# lv_io_pressure.net
KiCad netlist of a schematic drawn in Altium Designer
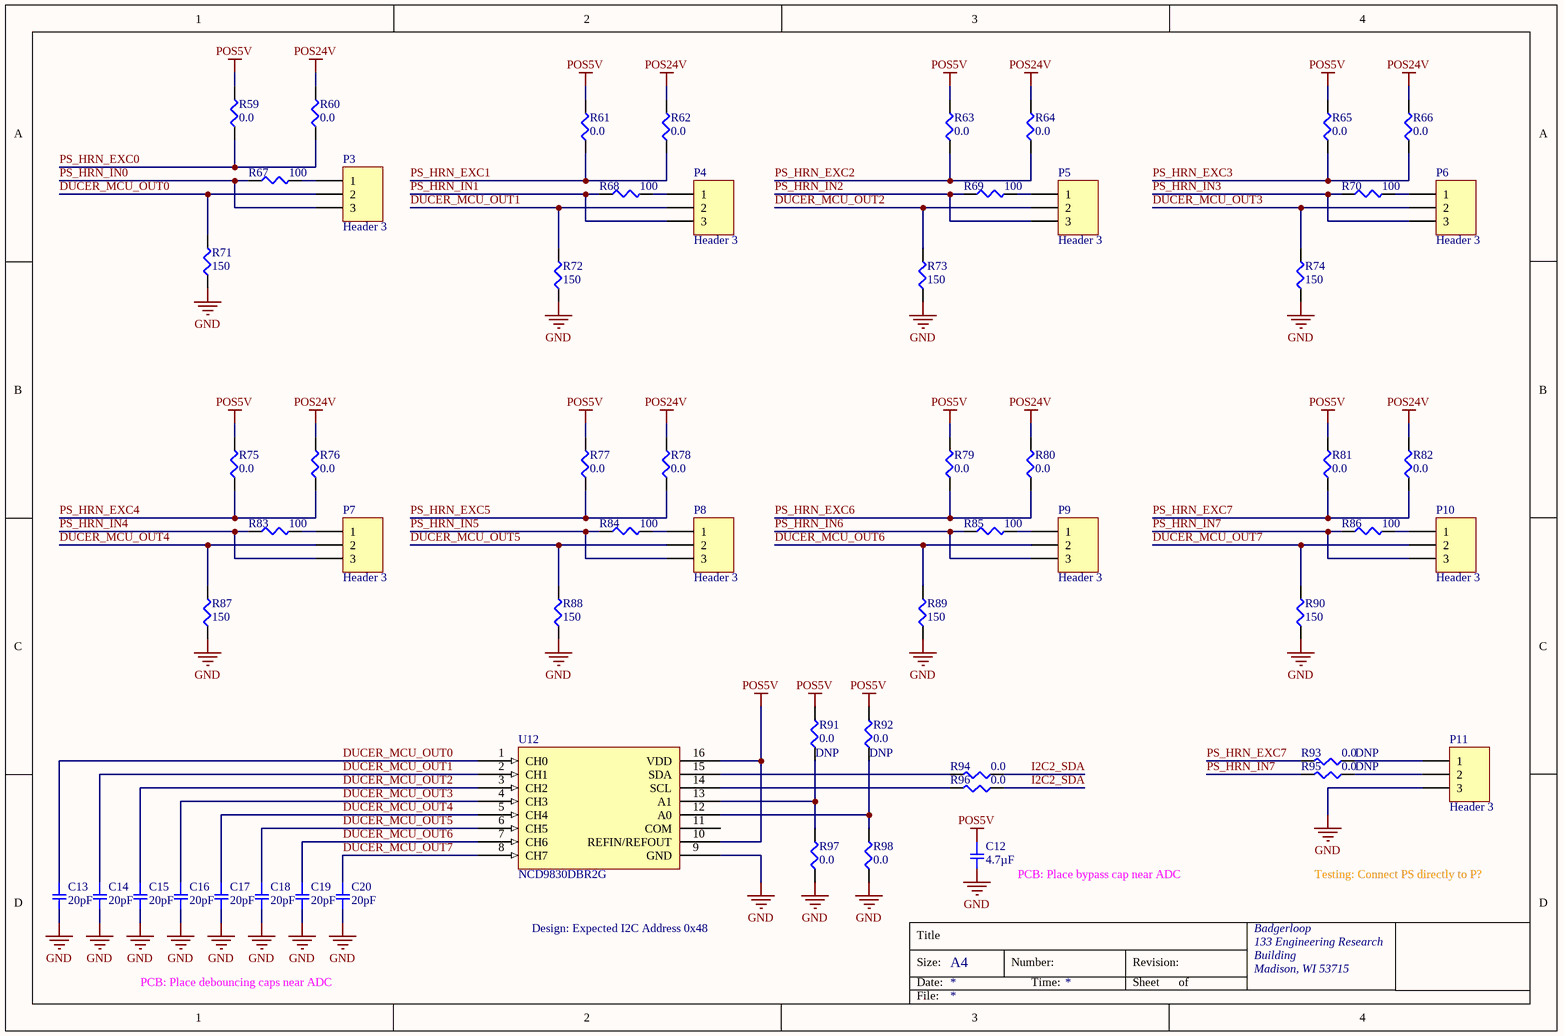
[diagram p0: lv_io_pressure.SchDoc]

(export (version "E")
  (design (tool "Eeschema 10.0.6"))
  (components
    (comp (ref "C12")
      (value "4.7µF")
      (footprint "SMD-0805C")
      (description "CAP CER 4.7UF 6.3V X5R 0805")
      (fields
        (field (name "DIGI-KEY PART NUMBER") "490-9749-1-ND")
        (field (name "PART NUMBER") "GRM21BR60J475KA11L")
      )
      (libsource (lib "capacitor") (part "GRM21BR60J475KA11L"))
    )
    (comp (ref "C13")
      (value "20pF")
      (footprint "SMD-0402C")
      (description "CAP CER 20PF 50V NP0 0402")
      (fields
        (field (name "DIGI-KEY PART NUMBER") "490-3120-1-ND")
        (field (name "PART NUMBER") "GJM1555C1H200JB01D")
      )
      (libsource (lib "capacitor") (part "GJM1555C1H200JB01D"))
    )
    (comp (ref "C14")
      (value "20pF")
      (footprint "SMD-0402C")
      (description "CAP CER 20PF 50V NP0 0402")
      (fields
        (field (name "DIGI-KEY PART NUMBER") "490-3120-1-ND")
        (field (name "PART NUMBER") "GJM1555C1H200JB01D")
      )
      (libsource (lib "capacitor") (part "GJM1555C1H200JB01D"))
    )
    (comp (ref "C15")
      (value "20pF")
      (footprint "SMD-0402C")
      (description "CAP CER 20PF 50V NP0 0402")
      (fields
        (field (name "DIGI-KEY PART NUMBER") "490-3120-1-ND")
        (field (name "PART NUMBER") "GJM1555C1H200JB01D")
      )
      (libsource (lib "capacitor") (part "GJM1555C1H200JB01D"))
    )
    (comp (ref "C16")
      (value "20pF")
      (footprint "SMD-0402C")
      (description "CAP CER 20PF 50V NP0 0402")
      (fields
        (field (name "DIGI-KEY PART NUMBER") "490-3120-1-ND")
        (field (name "PART NUMBER") "GJM1555C1H200JB01D")
      )
      (libsource (lib "capacitor") (part "GJM1555C1H200JB01D"))
    )
    (comp (ref "C17")
      (value "20pF")
      (footprint "SMD-0402C")
      (description "CAP CER 20PF 50V NP0 0402")
      (fields
        (field (name "DIGI-KEY PART NUMBER") "490-3120-1-ND")
        (field (name "PART NUMBER") "GJM1555C1H200JB01D")
      )
      (libsource (lib "capacitor") (part "GJM1555C1H200JB01D"))
    )
    (comp (ref "C18")
      (value "20pF")
      (footprint "SMD-0402C")
      (description "CAP CER 20PF 50V NP0 0402")
      (fields
        (field (name "DIGI-KEY PART NUMBER") "490-3120-1-ND")
        (field (name "PART NUMBER") "GJM1555C1H200JB01D")
      )
      (libsource (lib "capacitor") (part "GJM1555C1H200JB01D"))
    )
    (comp (ref "C19")
      (value "20pF")
      (footprint "SMD-0402C")
      (description "CAP CER 20PF 50V NP0 0402")
      (fields
        (field (name "DIGI-KEY PART NUMBER") "490-3120-1-ND")
        (field (name "PART NUMBER") "GJM1555C1H200JB01D")
      )
      (libsource (lib "capacitor") (part "GJM1555C1H200JB01D"))
    )
    (comp (ref "C20")
      (value "20pF")
      (footprint "SMD-0402C")
      (description "CAP CER 20PF 50V NP0 0402")
      (fields
        (field (name "DIGI-KEY PART NUMBER") "490-3120-1-ND")
        (field (name "PART NUMBER") "GJM1555C1H200JB01D")
      )
      (libsource (lib "capacitor") (part "GJM1555C1H200JB01D"))
    )
    (comp (ref "P3")
      (value "Header 3")
      (footprint "Pin Header 1x3 TH Pitch 2.54mm")
      (description "Header, 3-Pin")
      (fields (field (name "PUBLISHER") "Altium Limited"))
      (libsource (lib "connector") (part "Header 3"))
    )
    (comp (ref "P4")
      (value "Header 3")
      (footprint "Pin Header 1x3 TH Pitch 2.54mm")
      (description "Header, 3-Pin")
      (fields (field (name "PUBLISHER") "Altium Limited"))
      (libsource (lib "connector") (part "Header 3"))
    )
    (comp (ref "P5")
      (value "Header 3")
      (footprint "Pin Header 1x3 TH Pitch 2.54mm")
      (description "Header, 3-Pin")
      (fields (field (name "PUBLISHER") "Altium Limited"))
      (libsource (lib "connector") (part "Header 3"))
    )
    (comp (ref "P6")
      (value "Header 3")
      (footprint "Pin Header 1x3 TH Pitch 2.54mm")
      (description "Header, 3-Pin")
      (fields (field (name "PUBLISHER") "Altium Limited"))
      (libsource (lib "connector") (part "Header 3"))
    )
    (comp (ref "P7")
      (value "Header 3")
      (footprint "Pin Header 1x3 TH Pitch 2.54mm")
      (description "Header, 3-Pin")
      (fields (field (name "PUBLISHER") "Altium Limited"))
      (libsource (lib "connector") (part "Header 3"))
    )
    (comp (ref "P8")
      (value "Header 3")
      (footprint "Pin Header 1x3 TH Pitch 2.54mm")
      (description "Header, 3-Pin")
      (fields (field (name "PUBLISHER") "Altium Limited"))
      (libsource (lib "connector") (part "Header 3"))
    )
    (comp (ref "P9")
      (value "Header 3")
      (footprint "Pin Header 1x3 TH Pitch 2.54mm")
      (description "Header, 3-Pin")
      (fields (field (name "PUBLISHER") "Altium Limited"))
      (libsource (lib "connector") (part "Header 3"))
    )
    (comp (ref "P10")
      (value "Header 3")
      (footprint "Pin Header 1x3 TH Pitch 2.54mm")
      (description "Header, 3-Pin")
      (fields (field (name "PUBLISHER") "Altium Limited"))
      (libsource (lib "connector") (part "Header 3"))
    )
    (comp (ref "P11")
      (value "Header 3")
      (footprint "Pin Header 1x3 TH Pitch 2.54mm")
      (description "Header, 3-Pin")
      (fields (field (name "PUBLISHER") "Altium Limited"))
      (libsource (lib "connector") (part "Header 3"))
    )
    (comp (ref "R59")
      (value "0.0")
      (footprint "SMD-0402-RES")
      (description "RES SMD 0.0OHM JUMPER 1/10W 0402")
      (fields (field (name "PART NUMBER") "ERJ-2GE0R00X") (field (name "DIGI-KEY PART NUMBER") "P0.0JCT-ND"))
      (libsource (lib "resistor") (part "ERJ-2GE0R00X"))
    )
    (comp (ref "R60")
      (value "0.0")
      (footprint "SMD-0402-RES")
      (description "RES SMD 0.0OHM JUMPER 1/10W 0402")
      (fields (field (name "PART NUMBER") "ERJ-2GE0R00X") (field (name "DIGI-KEY PART NUMBER") "P0.0JCT-ND"))
      (libsource (lib "resistor") (part "ERJ-2GE0R00X"))
    )
    (comp (ref "R61")
      (value "0.0")
      (footprint "SMD-0402-RES")
      (description "RES SMD 0.0OHM JUMPER 1/10W 0402")
      (fields (field (name "PART NUMBER") "ERJ-2GE0R00X") (field (name "DIGI-KEY PART NUMBER") "P0.0JCT-ND"))
      (libsource (lib "resistor") (part "ERJ-2GE0R00X"))
    )
    (comp (ref "R62")
      (value "0.0")
      (footprint "SMD-0402-RES")
      (description "RES SMD 0.0OHM JUMPER 1/10W 0402")
      (fields (field (name "PART NUMBER") "ERJ-2GE0R00X") (field (name "DIGI-KEY PART NUMBER") "P0.0JCT-ND"))
      (libsource (lib "resistor") (part "ERJ-2GE0R00X"))
    )
    (comp (ref "R63")
      (value "0.0")
      (footprint "SMD-0402-RES")
      (description "RES SMD 0.0OHM JUMPER 1/10W 0402")
      (fields (field (name "PART NUMBER") "ERJ-2GE0R00X") (field (name "DIGI-KEY PART NUMBER") "P0.0JCT-ND"))
      (libsource (lib "resistor") (part "ERJ-2GE0R00X"))
    )
    (comp (ref "R64")
      (value "0.0")
      (footprint "SMD-0402-RES")
      (description "RES SMD 0.0OHM JUMPER 1/10W 0402")
      (fields (field (name "PART NUMBER") "ERJ-2GE0R00X") (field (name "DIGI-KEY PART NUMBER") "P0.0JCT-ND"))
      (libsource (lib "resistor") (part "ERJ-2GE0R00X"))
    )
    (comp (ref "R65")
      (value "0.0")
      (footprint "SMD-0402-RES")
      (description "RES SMD 0.0OHM JUMPER 1/10W 0402")
      (fields (field (name "PART NUMBER") "ERJ-2GE0R00X") (field (name "DIGI-KEY PART NUMBER") "P0.0JCT-ND"))
      (libsource (lib "resistor") (part "ERJ-2GE0R00X"))
    )
    (comp (ref "R66")
      (value "0.0")
      (footprint "SMD-0402-RES")
      (description "RES SMD 0.0OHM JUMPER 1/10W 0402")
      (fields (field (name "PART NUMBER") "ERJ-2GE0R00X") (field (name "DIGI-KEY PART NUMBER") "P0.0JCT-ND"))
      (libsource (lib "resistor") (part "ERJ-2GE0R00X"))
    )
    (comp (ref "R67")
      (value "100")
      (footprint "SMD-0402-RES")
      (description "RES SMD 100 OHM 5% 1/10W 0402")
      (fields (field (name "PART NUMBER") "ERJ-2GEJ101X") (field (name "DIGI-KEY PART NUMBER") "P100JCT-ND"))
      (libsource (lib "resistor") (part "ERJ-2GEJ101X"))
    )
    (comp (ref "R68")
      (value "100")
      (footprint "SMD-0402-RES")
      (description "RES SMD 100 OHM 5% 1/10W 0402")
      (fields (field (name "PART NUMBER") "ERJ-2GEJ101X") (field (name "DIGI-KEY PART NUMBER") "P100JCT-ND"))
      (libsource (lib "resistor") (part "ERJ-2GEJ101X"))
    )
    (comp (ref "R69")
      (value "100")
      (footprint "SMD-0402-RES")
      (description "RES SMD 100 OHM 5% 1/10W 0402")
      (fields (field (name "PART NUMBER") "ERJ-2GEJ101X") (field (name "DIGI-KEY PART NUMBER") "P100JCT-ND"))
      (libsource (lib "resistor") (part "ERJ-2GEJ101X"))
    )
    (comp (ref "R70")
      (value "100")
      (footprint "SMD-0402-RES")
      (description "RES SMD 100 OHM 5% 1/10W 0402")
      (fields (field (name "PART NUMBER") "ERJ-2GEJ101X") (field (name "DIGI-KEY PART NUMBER") "P100JCT-ND"))
      (libsource (lib "resistor") (part "ERJ-2GEJ101X"))
    )
    (comp (ref "R71")
      (value "150")
      (footprint "SMD-0603-RES")
      (description "RES SMD 150 OHM 0.5% 1/5W 0603")
      (fields
        (field (name "PART NUMBER") "ERJ-P03D1500V")
        (field (name "DIGI-KEY PART NUMBER") "P16013CT-ND")
      )
      (libsource (lib "resistor") (part "ERJ-P03D1500V"))
    )
    (comp (ref "R72")
      (value "150")
      (footprint "SMD-0603-RES")
      (description "RES SMD 150 OHM 0.5% 1/5W 0603")
      (fields
        (field (name "PART NUMBER") "ERJ-P03D1500V")
        (field (name "DIGI-KEY PART NUMBER") "P16013CT-ND")
      )
      (libsource (lib "resistor") (part "ERJ-P03D1500V"))
    )
    (comp (ref "R73")
      (value "150")
      (footprint "SMD-0603-RES")
      (description "RES SMD 150 OHM 0.5% 1/5W 0603")
      (fields
        (field (name "PART NUMBER") "ERJ-P03D1500V")
        (field (name "DIGI-KEY PART NUMBER") "P16013CT-ND")
      )
      (libsource (lib "resistor") (part "ERJ-P03D1500V"))
    )
    (comp (ref "R74")
      (value "150")
      (footprint "SMD-0603-RES")
      (description "RES SMD 150 OHM 0.5% 1/5W 0603")
      (fields
        (field (name "PART NUMBER") "ERJ-P03D1500V")
        (field (name "DIGI-KEY PART NUMBER") "P16013CT-ND")
      )
      (libsource (lib "resistor") (part "ERJ-P03D1500V"))
    )
    (comp (ref "R75")
      (value "0.0")
      (footprint "SMD-0402-RES")
      (description "RES SMD 0.0OHM JUMPER 1/10W 0402")
      (fields (field (name "PART NUMBER") "ERJ-2GE0R00X") (field (name "DIGI-KEY PART NUMBER") "P0.0JCT-ND"))
      (libsource (lib "resistor") (part "ERJ-2GE0R00X"))
    )
    (comp (ref "R76")
      (value "0.0")
      (footprint "SMD-0402-RES")
      (description "RES SMD 0.0OHM JUMPER 1/10W 0402")
      (fields (field (name "PART NUMBER") "ERJ-2GE0R00X") (field (name "DIGI-KEY PART NUMBER") "P0.0JCT-ND"))
      (libsource (lib "resistor") (part "ERJ-2GE0R00X"))
    )
    (comp (ref "R77")
      (value "0.0")
      (footprint "SMD-0402-RES")
      (description "RES SMD 0.0OHM JUMPER 1/10W 0402")
      (fields (field (name "PART NUMBER") "ERJ-2GE0R00X") (field (name "DIGI-KEY PART NUMBER") "P0.0JCT-ND"))
      (libsource (lib "resistor") (part "ERJ-2GE0R00X"))
    )
    (comp (ref "R78")
      (value "0.0")
      (footprint "SMD-0402-RES")
      (description "RES SMD 0.0OHM JUMPER 1/10W 0402")
      (fields (field (name "PART NUMBER") "ERJ-2GE0R00X") (field (name "DIGI-KEY PART NUMBER") "P0.0JCT-ND"))
      (libsource (lib "resistor") (part "ERJ-2GE0R00X"))
    )
    (comp (ref "R79")
      (value "0.0")
      (footprint "SMD-0402-RES")
      (description "RES SMD 0.0OHM JUMPER 1/10W 0402")
      (fields (field (name "PART NUMBER") "ERJ-2GE0R00X") (field (name "DIGI-KEY PART NUMBER") "P0.0JCT-ND"))
      (libsource (lib "resistor") (part "ERJ-2GE0R00X"))
    )
    (comp (ref "R80")
      (value "0.0")
      (footprint "SMD-0402-RES")
      (description "RES SMD 0.0OHM JUMPER 1/10W 0402")
      (fields (field (name "PART NUMBER") "ERJ-2GE0R00X") (field (name "DIGI-KEY PART NUMBER") "P0.0JCT-ND"))
      (libsource (lib "resistor") (part "ERJ-2GE0R00X"))
    )
    (comp (ref "R81")
      (value "0.0")
      (footprint "SMD-0402-RES")
      (description "RES SMD 0.0OHM JUMPER 1/10W 0402")
      (fields (field (name "PART NUMBER") "ERJ-2GE0R00X") (field (name "DIGI-KEY PART NUMBER") "P0.0JCT-ND"))
      (libsource (lib "resistor") (part "ERJ-2GE0R00X"))
    )
    (comp (ref "R82")
      (value "0.0")
      (footprint "SMD-0402-RES")
      (description "RES SMD 0.0OHM JUMPER 1/10W 0402")
      (fields (field (name "PART NUMBER") "ERJ-2GE0R00X") (field (name "DIGI-KEY PART NUMBER") "P0.0JCT-ND"))
      (libsource (lib "resistor") (part "ERJ-2GE0R00X"))
    )
    (comp (ref "R83")
      (value "100")
      (footprint "SMD-0402-RES")
      (description "RES SMD 100 OHM 5% 1/10W 0402")
      (fields (field (name "PART NUMBER") "ERJ-2GEJ101X") (field (name "DIGI-KEY PART NUMBER") "P100JCT-ND"))
      (libsource (lib "resistor") (part "ERJ-2GEJ101X"))
    )
    (comp (ref "R84")
      (value "100")
      (footprint "SMD-0402-RES")
      (description "RES SMD 100 OHM 5% 1/10W 0402")
      (fields (field (name "PART NUMBER") "ERJ-2GEJ101X") (field (name "DIGI-KEY PART NUMBER") "P100JCT-ND"))
      (libsource (lib "resistor") (part "ERJ-2GEJ101X"))
    )
    (comp (ref "R85")
      (value "100")
      (footprint "SMD-0402-RES")
      (description "RES SMD 100 OHM 5% 1/10W 0402")
      (fields (field (name "PART NUMBER") "ERJ-2GEJ101X") (field (name "DIGI-KEY PART NUMBER") "P100JCT-ND"))
      (libsource (lib "resistor") (part "ERJ-2GEJ101X"))
    )
    (comp (ref "R86")
      (value "100")
      (footprint "SMD-0402-RES")
      (description "RES SMD 100 OHM 5% 1/10W 0402")
      (fields (field (name "PART NUMBER") "ERJ-2GEJ101X") (field (name "DIGI-KEY PART NUMBER") "P100JCT-ND"))
      (libsource (lib "resistor") (part "ERJ-2GEJ101X"))
    )
    (comp (ref "R87")
      (value "150")
      (footprint "SMD-0603-RES")
      (description "RES SMD 150 OHM 0.5% 1/5W 0603")
      (fields
        (field (name "PART NUMBER") "ERJ-P03D1500V")
        (field (name "DIGI-KEY PART NUMBER") "P16013CT-ND")
      )
      (libsource (lib "resistor") (part "ERJ-P03D1500V"))
    )
    (comp (ref "R88")
      (value "150")
      (footprint "SMD-0603-RES")
      (description "RES SMD 150 OHM 0.5% 1/5W 0603")
      (fields
        (field (name "PART NUMBER") "ERJ-P03D1500V")
        (field (name "DIGI-KEY PART NUMBER") "P16013CT-ND")
      )
      (libsource (lib "resistor") (part "ERJ-P03D1500V"))
    )
    (comp (ref "R89")
      (value "150")
      (footprint "SMD-0603-RES")
      (description "RES SMD 150 OHM 0.5% 1/5W 0603")
      (fields
        (field (name "PART NUMBER") "ERJ-P03D1500V")
        (field (name "DIGI-KEY PART NUMBER") "P16013CT-ND")
      )
      (libsource (lib "resistor") (part "ERJ-P03D1500V"))
    )
    (comp (ref "R90")
      (value "150")
      (footprint "SMD-0603-RES")
      (description "RES SMD 150 OHM 0.5% 1/5W 0603")
      (fields
        (field (name "PART NUMBER") "ERJ-P03D1500V")
        (field (name "DIGI-KEY PART NUMBER") "P16013CT-ND")
      )
      (libsource (lib "resistor") (part "ERJ-P03D1500V"))
    )
    (comp (ref "R91")
      (value "0.0")
      (footprint "SMD-0402-RES")
      (description "RES SMD 0.0OHM JUMPER 1/10W 0402")
      (fields
        (field (name "PART NUMBER") "ERJ-2GE0R00X")
        (field (name "DIGI-KEY PART NUMBER") "P0.0JCT-ND")
        (field (name "DNP") "DNP")
      )
      (libsource (lib "resistor") (part "ERJ-2GE0R00X"))
    )
    (comp (ref "R92")
      (value "0.0")
      (footprint "SMD-0402-RES")
      (description "RES SMD 0.0OHM JUMPER 1/10W 0402")
      (fields
        (field (name "PART NUMBER") "ERJ-2GE0R00X")
        (field (name "DIGI-KEY PART NUMBER") "P0.0JCT-ND")
        (field (name "DNP") "DNP")
      )
      (libsource (lib "resistor") (part "ERJ-2GE0R00X"))
    )
    (comp (ref "R93")
      (value "0.0")
      (footprint "SMD-0402-RES")
      (description "RES SMD 0.0OHM JUMPER 1/10W 0402")
      (fields
        (field (name "PART NUMBER") "ERJ-2GE0R00X")
        (field (name "DIGI-KEY PART NUMBER") "P0.0JCT-ND")
        (field (name "DNP") "DNP")
      )
      (libsource (lib "resistor") (part "ERJ-2GE0R00X"))
    )
    (comp (ref "R94")
      (value "0.0")
      (footprint "SMD-0402-RES")
      (description "RES SMD 0.0OHM JUMPER 1/10W 0402")
      (fields (field (name "PART NUMBER") "ERJ-2GE0R00X") (field (name "DIGI-KEY PART NUMBER") "P0.0JCT-ND"))
      (libsource (lib "resistor") (part "ERJ-2GE0R00X"))
    )
    (comp (ref "R95")
      (value "0.0")
      (footprint "SMD-0402-RES")
      (description "RES SMD 0.0OHM JUMPER 1/10W 0402")
      (fields
        (field (name "PART NUMBER") "ERJ-2GE0R00X")
        (field (name "DIGI-KEY PART NUMBER") "P0.0JCT-ND")
        (field (name "DNP") "DNP")
      )
      (libsource (lib "") (part "ERJ-2GE0R00X_1"))
    )
    (comp (ref "R96")
      (value "0.0")
      (footprint "SMD-0402-RES")
      (description "RES SMD 0.0OHM JUMPER 1/10W 0402")
      (fields (field (name "PART NUMBER") "ERJ-2GE0R00X") (field (name "DIGI-KEY PART NUMBER") "P0.0JCT-ND"))
      (libsource (lib "resistor") (part "ERJ-2GE0R00X"))
    )
    (comp (ref "R97")
      (value "0.0")
      (footprint "SMD-0402-RES")
      (description "RES SMD 0.0OHM JUMPER 1/10W 0402")
      (fields (field (name "PART NUMBER") "ERJ-2GE0R00X") (field (name "DIGI-KEY PART NUMBER") "P0.0JCT-ND"))
      (libsource (lib "resistor") (part "ERJ-2GE0R00X"))
    )
    (comp (ref "R98")
      (value "0.0")
      (footprint "SMD-0402-RES")
      (description "RES SMD 0.0OHM JUMPER 1/10W 0402")
      (fields (field (name "PART NUMBER") "ERJ-2GE0R00X") (field (name "DIGI-KEY PART NUMBER") "P0.0JCT-ND"))
      (libsource (lib "resistor") (part "ERJ-2GE0R00X"))
    )
    (comp (ref "U12")
      (value "NCD9830DBR2G")
      (description "IC ADC 8BIT 8CH I2C 16TSSOP")
      (fields (field (name "MANUFACTURER") "ON Semiconductor"))
      (libsource (lib "ic") (part "NCD9830DBR2G"))
    )
  )
  (nets
    (net (code "1") (name "/DUCER_MCU_OUT0") (class "Default")
      (node (ref "C13") (pin "1") (pinfunction "1_1") (pintype "passive"))
      (node (ref "P3") (pin "2") (pinfunction "2_2") (pintype "passive"))
      (node (ref "R71") (pin "2") (pinfunction "2_2") (pintype "passive"))
      (node (ref "U12") (pin "1") (pinfunction "CH0_1") (pintype "input"))
    )
    (net (code "2") (name "/DUCER_MCU_OUT1") (class "Default")
      (node (ref "C14") (pin "1") (pinfunction "1_1") (pintype "passive"))
      (node (ref "P4") (pin "2") (pinfunction "2_2") (pintype "passive"))
      (node (ref "R72") (pin "2") (pinfunction "2_2") (pintype "passive"))
      (node (ref "U12") (pin "2") (pinfunction "CH1_2") (pintype "input"))
    )
    (net (code "3") (name "/DUCER_MCU_OUT2") (class "Default")
      (node (ref "C15") (pin "1") (pinfunction "1_1") (pintype "passive"))
      (node (ref "P5") (pin "2") (pinfunction "2_2") (pintype "passive"))
      (node (ref "R73") (pin "2") (pinfunction "2_2") (pintype "passive"))
      (node (ref "U12") (pin "3") (pinfunction "CH2_3") (pintype "input"))
    )
    (net (code "4") (name "/DUCER_MCU_OUT3") (class "Default")
      (node (ref "C16") (pin "1") (pinfunction "1_1") (pintype "passive"))
      (node (ref "P6") (pin "2") (pinfunction "2_2") (pintype "passive"))
      (node (ref "R74") (pin "2") (pinfunction "2_2") (pintype "passive"))
      (node (ref "U12") (pin "4") (pinfunction "CH3_4") (pintype "input"))
    )
    (net (code "5") (name "/DUCER_MCU_OUT4") (class "Default")
      (node (ref "C17") (pin "1") (pinfunction "1_1") (pintype "passive"))
      (node (ref "P7") (pin "2") (pinfunction "2_2") (pintype "passive"))
      (node (ref "R87") (pin "2") (pinfunction "2_2") (pintype "passive"))
      (node (ref "U12") (pin "5") (pinfunction "CH4_5") (pintype "input"))
    )
    (net (code "6") (name "/DUCER_MCU_OUT5") (class "Default")
      (node (ref "C18") (pin "1") (pinfunction "1_1") (pintype "passive"))
      (node (ref "P8") (pin "2") (pinfunction "2_2") (pintype "passive"))
      (node (ref "R88") (pin "2") (pinfunction "2_2") (pintype "passive"))
      (node (ref "U12") (pin "6") (pinfunction "CH5_6") (pintype "input"))
    )
    (net (code "7") (name "/DUCER_MCU_OUT6") (class "Default")
      (node (ref "C19") (pin "1") (pinfunction "1_1") (pintype "passive"))
      (node (ref "P9") (pin "2") (pinfunction "2_2") (pintype "passive"))
      (node (ref "R89") (pin "2") (pinfunction "2_2") (pintype "passive"))
      (node (ref "U12") (pin "7") (pinfunction "CH6_7") (pintype "input"))
    )
    (net (code "8") (name "/DUCER_MCU_OUT7") (class "Default")
      (node (ref "C20") (pin "1") (pinfunction "1_1") (pintype "passive"))
      (node (ref "P10") (pin "2") (pinfunction "2_2") (pintype "passive"))
      (node (ref "R90") (pin "2") (pinfunction "2_2") (pintype "passive"))
      (node (ref "U12") (pin "8") (pinfunction "CH7_8") (pintype "input"))
    )
    (net (code "9") (name "/I2C2_SDA") (class "Default")
      (node (ref "R94") (pin "1") (pinfunction "1_1") (pintype "passive"))
      (node (ref "R96") (pin "1") (pinfunction "1_1") (pintype "passive"))
    )
    (net (code "10") (name "/PS_HRN_EXC0") (class "Default")
      (node (ref "R59") (pin "1") (pinfunction "1_1") (pintype "passive"))
      (node (ref "R60") (pin "1") (pinfunction "1_1") (pintype "passive"))
    )
    (net (code "11") (name "/PS_HRN_EXC1") (class "Default")
      (node (ref "R61") (pin "1") (pinfunction "1_1") (pintype "passive"))
      (node (ref "R62") (pin "1") (pinfunction "1_1") (pintype "passive"))
    )
    (net (code "12") (name "/PS_HRN_EXC2") (class "Default")
      (node (ref "R63") (pin "1") (pinfunction "1_1") (pintype "passive"))
      (node (ref "R64") (pin "1") (pinfunction "1_1") (pintype "passive"))
    )
    (net (code "13") (name "/PS_HRN_EXC3") (class "Default")
      (node (ref "R65") (pin "1") (pinfunction "1_1") (pintype "passive"))
      (node (ref "R66") (pin "1") (pinfunction "1_1") (pintype "passive"))
    )
    (net (code "14") (name "/PS_HRN_EXC4") (class "Default")
      (node (ref "R75") (pin "1") (pinfunction "1_1") (pintype "passive"))
      (node (ref "R76") (pin "1") (pinfunction "1_1") (pintype "passive"))
    )
    (net (code "15") (name "/PS_HRN_EXC5") (class "Default")
      (node (ref "R77") (pin "1") (pinfunction "1_1") (pintype "passive"))
      (node (ref "R78") (pin "1") (pinfunction "1_1") (pintype "passive"))
    )
    (net (code "16") (name "/PS_HRN_EXC6") (class "Default")
      (node (ref "R79") (pin "1") (pinfunction "1_1") (pintype "passive"))
      (node (ref "R80") (pin "1") (pinfunction "1_1") (pintype "passive"))
    )
    (net (code "17") (name "/PS_HRN_EXC7") (class "Default")
      (node (ref "R81") (pin "1") (pinfunction "1_1") (pintype "passive"))
      (node (ref "R82") (pin "1") (pinfunction "1_1") (pintype "passive"))
      (node (ref "R93") (pin "2") (pinfunction "2_2") (pintype "passive"))
    )
    (net (code "18") (name "/PS_HRN_IN0") (class "Default")
      (node (ref "P3") (pin "3") (pinfunction "3_3") (pintype "passive"))
      (node (ref "R67") (pin "1") (pinfunction "1_1") (pintype "passive"))
    )
    (net (code "19") (name "/PS_HRN_IN1") (class "Default")
      (node (ref "P4") (pin "3") (pinfunction "3_3") (pintype "passive"))
      (node (ref "R68") (pin "1") (pinfunction "1_1") (pintype "passive"))
    )
    (net (code "20") (name "/PS_HRN_IN2") (class "Default")
      (node (ref "P5") (pin "3") (pinfunction "3_3") (pintype "passive"))
      (node (ref "R69") (pin "1") (pinfunction "1_1") (pintype "passive"))
    )
    (net (code "21") (name "/PS_HRN_IN3") (class "Default")
      (node (ref "P6") (pin "3") (pinfunction "3_3") (pintype "passive"))
      (node (ref "R70") (pin "1") (pinfunction "1_1") (pintype "passive"))
    )
    (net (code "22") (name "/PS_HRN_IN4") (class "Default")
      (node (ref "P7") (pin "3") (pinfunction "3_3") (pintype "passive"))
      (node (ref "R83") (pin "1") (pinfunction "1_1") (pintype "passive"))
    )
    (net (code "23") (name "/PS_HRN_IN5") (class "Default")
      (node (ref "P8") (pin "3") (pinfunction "3_3") (pintype "passive"))
      (node (ref "R84") (pin "1") (pinfunction "1_1") (pintype "passive"))
    )
    (net (code "24") (name "/PS_HRN_IN6") (class "Default")
      (node (ref "P9") (pin "3") (pinfunction "3_3") (pintype "passive"))
      (node (ref "R85") (pin "1") (pinfunction "1_1") (pintype "passive"))
    )
    (net (code "25") (name "/PS_HRN_IN7") (class "Default")
      (node (ref "P10") (pin "3") (pinfunction "3_3") (pintype "passive"))
      (node (ref "R86") (pin "1") (pinfunction "1_1") (pintype "passive"))
      (node (ref "R95") (pin "2") (pinfunction "2_2") (pintype "passive"))
    )
    (net (code "26") (name "GND") (class "Default")
      (node (ref "C12") (pin "2") (pinfunction "2_2") (pintype "passive"))
      (node (ref "C13") (pin "2") (pinfunction "2_2") (pintype "passive"))
      (node (ref "C14") (pin "2") (pinfunction "2_2") (pintype "passive"))
      (node (ref "C15") (pin "2") (pinfunction "2_2") (pintype "passive"))
      (node (ref "C16") (pin "2") (pinfunction "2_2") (pintype "passive"))
      (node (ref "C17") (pin "2") (pinfunction "2_2") (pintype "passive"))
      (node (ref "C18") (pin "2") (pinfunction "2_2") (pintype "passive"))
      (node (ref "C19") (pin "2") (pinfunction "2_2") (pintype "passive"))
      (node (ref "C20") (pin "2") (pinfunction "2_2") (pintype "passive"))
      (node (ref "P11") (pin "3") (pinfunction "3_3") (pintype "passive"))
      (node (ref "R71") (pin "1") (pinfunction "1_1") (pintype "passive"))
      (node (ref "R72") (pin "1") (pinfunction "1_1") (pintype "passive"))
      (node (ref "R73") (pin "1") (pinfunction "1_1") (pintype "passive"))
      (node (ref "R74") (pin "1") (pinfunction "1_1") (pintype "passive"))
      (node (ref "R87") (pin "1") (pinfunction "1_1") (pintype "passive"))
      (node (ref "R88") (pin "1") (pinfunction "1_1") (pintype "passive"))
      (node (ref "R89") (pin "1") (pinfunction "1_1") (pintype "passive"))
      (node (ref "R90") (pin "1") (pinfunction "1_1") (pintype "passive"))
      (node (ref "R97") (pin "1") (pinfunction "1_1") (pintype "passive"))
      (node (ref "R98") (pin "1") (pinfunction "1_1") (pintype "passive"))
      (node (ref "U12") (pin "9") (pinfunction "GND_9") (pintype "power_in"))
    )
    (net (code "27") (name "Net-(P3-Pad1)") (class "Default")
      (node (ref "P3") (pin "1") (pinfunction "1_1") (pintype "passive"))
      (node (ref "R67") (pin "2") (pinfunction "2_2") (pintype "passive"))
    )
    (net (code "28") (name "Net-(P4-Pad1)") (class "Default")
      (node (ref "P4") (pin "1") (pinfunction "1_1") (pintype "passive"))
      (node (ref "R68") (pin "2") (pinfunction "2_2") (pintype "passive"))
    )
    (net (code "29") (name "Net-(P5-Pad1)") (class "Default")
      (node (ref "P5") (pin "1") (pinfunction "1_1") (pintype "passive"))
      (node (ref "R69") (pin "2") (pinfunction "2_2") (pintype "passive"))
    )
    (net (code "30") (name "Net-(P6-Pad1)") (class "Default")
      (node (ref "P6") (pin "1") (pinfunction "1_1") (pintype "passive"))
      (node (ref "R70") (pin "2") (pinfunction "2_2") (pintype "passive"))
    )
    (net (code "31") (name "Net-(P7-Pad1)") (class "Default")
      (node (ref "P7") (pin "1") (pinfunction "1_1") (pintype "passive"))
      (node (ref "R83") (pin "2") (pinfunction "2_2") (pintype "passive"))
    )
    (net (code "32") (name "Net-(P8-Pad1)") (class "Default")
      (node (ref "P8") (pin "1") (pinfunction "1_1") (pintype "passive"))
      (node (ref "R84") (pin "2") (pinfunction "2_2") (pintype "passive"))
    )
    (net (code "33") (name "Net-(P9-Pad1)") (class "Default")
      (node (ref "P9") (pin "1") (pinfunction "1_1") (pintype "passive"))
      (node (ref "R85") (pin "2") (pinfunction "2_2") (pintype "passive"))
    )
    (net (code "34") (name "Net-(P10-Pad1)") (class "Default")
      (node (ref "P10") (pin "1") (pinfunction "1_1") (pintype "passive"))
      (node (ref "R86") (pin "2") (pinfunction "2_2") (pintype "passive"))
    )
    (net (code "35") (name "Net-(P11-Pad1)") (class "Default")
      (node (ref "P11") (pin "1") (pinfunction "1_1") (pintype "passive"))
      (node (ref "R93") (pin "1") (pinfunction "1_1") (pintype "passive"))
    )
    (net (code "36") (name "Net-(P11-Pad2)") (class "Default")
      (node (ref "P11") (pin "2") (pinfunction "2_2") (pintype "passive"))
      (node (ref "R95") (pin "1") (pinfunction "1_1") (pintype "passive"))
    )
    (net (code "37") (name "Net-(U12-A0)") (class "Default")
      (node (ref "R92") (pin "1") (pinfunction "1_1") (pintype "passive"))
      (node (ref "R98") (pin "2") (pinfunction "2_2") (pintype "passive"))
      (node (ref "U12") (pin "12") (pinfunction "A0_12") (pintype "passive"))
    )
    (net (code "38") (name "Net-(U12-A1)") (class "Default")
      (node (ref "R91") (pin "1") (pinfunction "1_1") (pintype "passive"))
      (node (ref "R97") (pin "2") (pinfunction "2_2") (pintype "passive"))
      (node (ref "U12") (pin "13") (pinfunction "A1_13") (pintype "passive"))
    )
    (net (code "39") (name "Net-(U12-SCL)") (class "Default")
      (node (ref "R96") (pin "2") (pinfunction "2_2") (pintype "passive"))
      (node (ref "U12") (pin "14") (pinfunction "SCL_14") (pintype "passive"))
    )
    (net (code "40") (name "Net-(U12-SDA)") (class "Default")
      (node (ref "R94") (pin "2") (pinfunction "2_2") (pintype "passive"))
      (node (ref "U12") (pin "15") (pinfunction "SDA_15") (pintype "passive"))
    )
    (net (code "41") (name "POS5V") (class "Default")
      (node (ref "C12") (pin "1") (pinfunction "1_1") (pintype "passive"))
      (node (ref "R59") (pin "2") (pinfunction "2_2") (pintype "passive"))
      (node (ref "R61") (pin "2") (pinfunction "2_2") (pintype "passive"))
      (node (ref "R63") (pin "2") (pinfunction "2_2") (pintype "passive"))
      (node (ref "R65") (pin "2") (pinfunction "2_2") (pintype "passive"))
      (node (ref "R75") (pin "2") (pinfunction "2_2") (pintype "passive"))
      (node (ref "R77") (pin "2") (pinfunction "2_2") (pintype "passive"))
      (node (ref "R79") (pin "2") (pinfunction "2_2") (pintype "passive"))
      (node (ref "R81") (pin "2") (pinfunction "2_2") (pintype "passive"))
      (node (ref "R91") (pin "2") (pinfunction "2_2") (pintype "passive"))
      (node (ref "R92") (pin "2") (pinfunction "2_2") (pintype "passive"))
      (node (ref "U12") (pin "10") (pinfunction "REFIN/REFOUT_10") (pintype "power_in"))
      (node (ref "U12") (pin "16") (pinfunction "VDD_16") (pintype "power_in"))
    )
    (net (code "42") (name "POS24V") (class "Default")
      (node (ref "R60") (pin "2") (pinfunction "2_2") (pintype "passive"))
      (node (ref "R62") (pin "2") (pinfunction "2_2") (pintype "passive"))
      (node (ref "R64") (pin "2") (pinfunction "2_2") (pintype "passive"))
      (node (ref "R66") (pin "2") (pinfunction "2_2") (pintype "passive"))
      (node (ref "R76") (pin "2") (pinfunction "2_2") (pintype "passive"))
      (node (ref "R78") (pin "2") (pinfunction "2_2") (pintype "passive"))
      (node (ref "R80") (pin "2") (pinfunction "2_2") (pintype "passive"))
      (node (ref "R82") (pin "2") (pinfunction "2_2") (pintype "passive"))
    )
    (net (code "43") (name "unconnected-(U12-COM-Pad11)") (class "Default")
      (node (ref "U12") (pin "11") (pinfunction "COM_11") (pintype "power_in"))
    )
  )
)
